# Placa_FdC_v2.net
KiCad netlist of a schematic drawn in Altium Designer
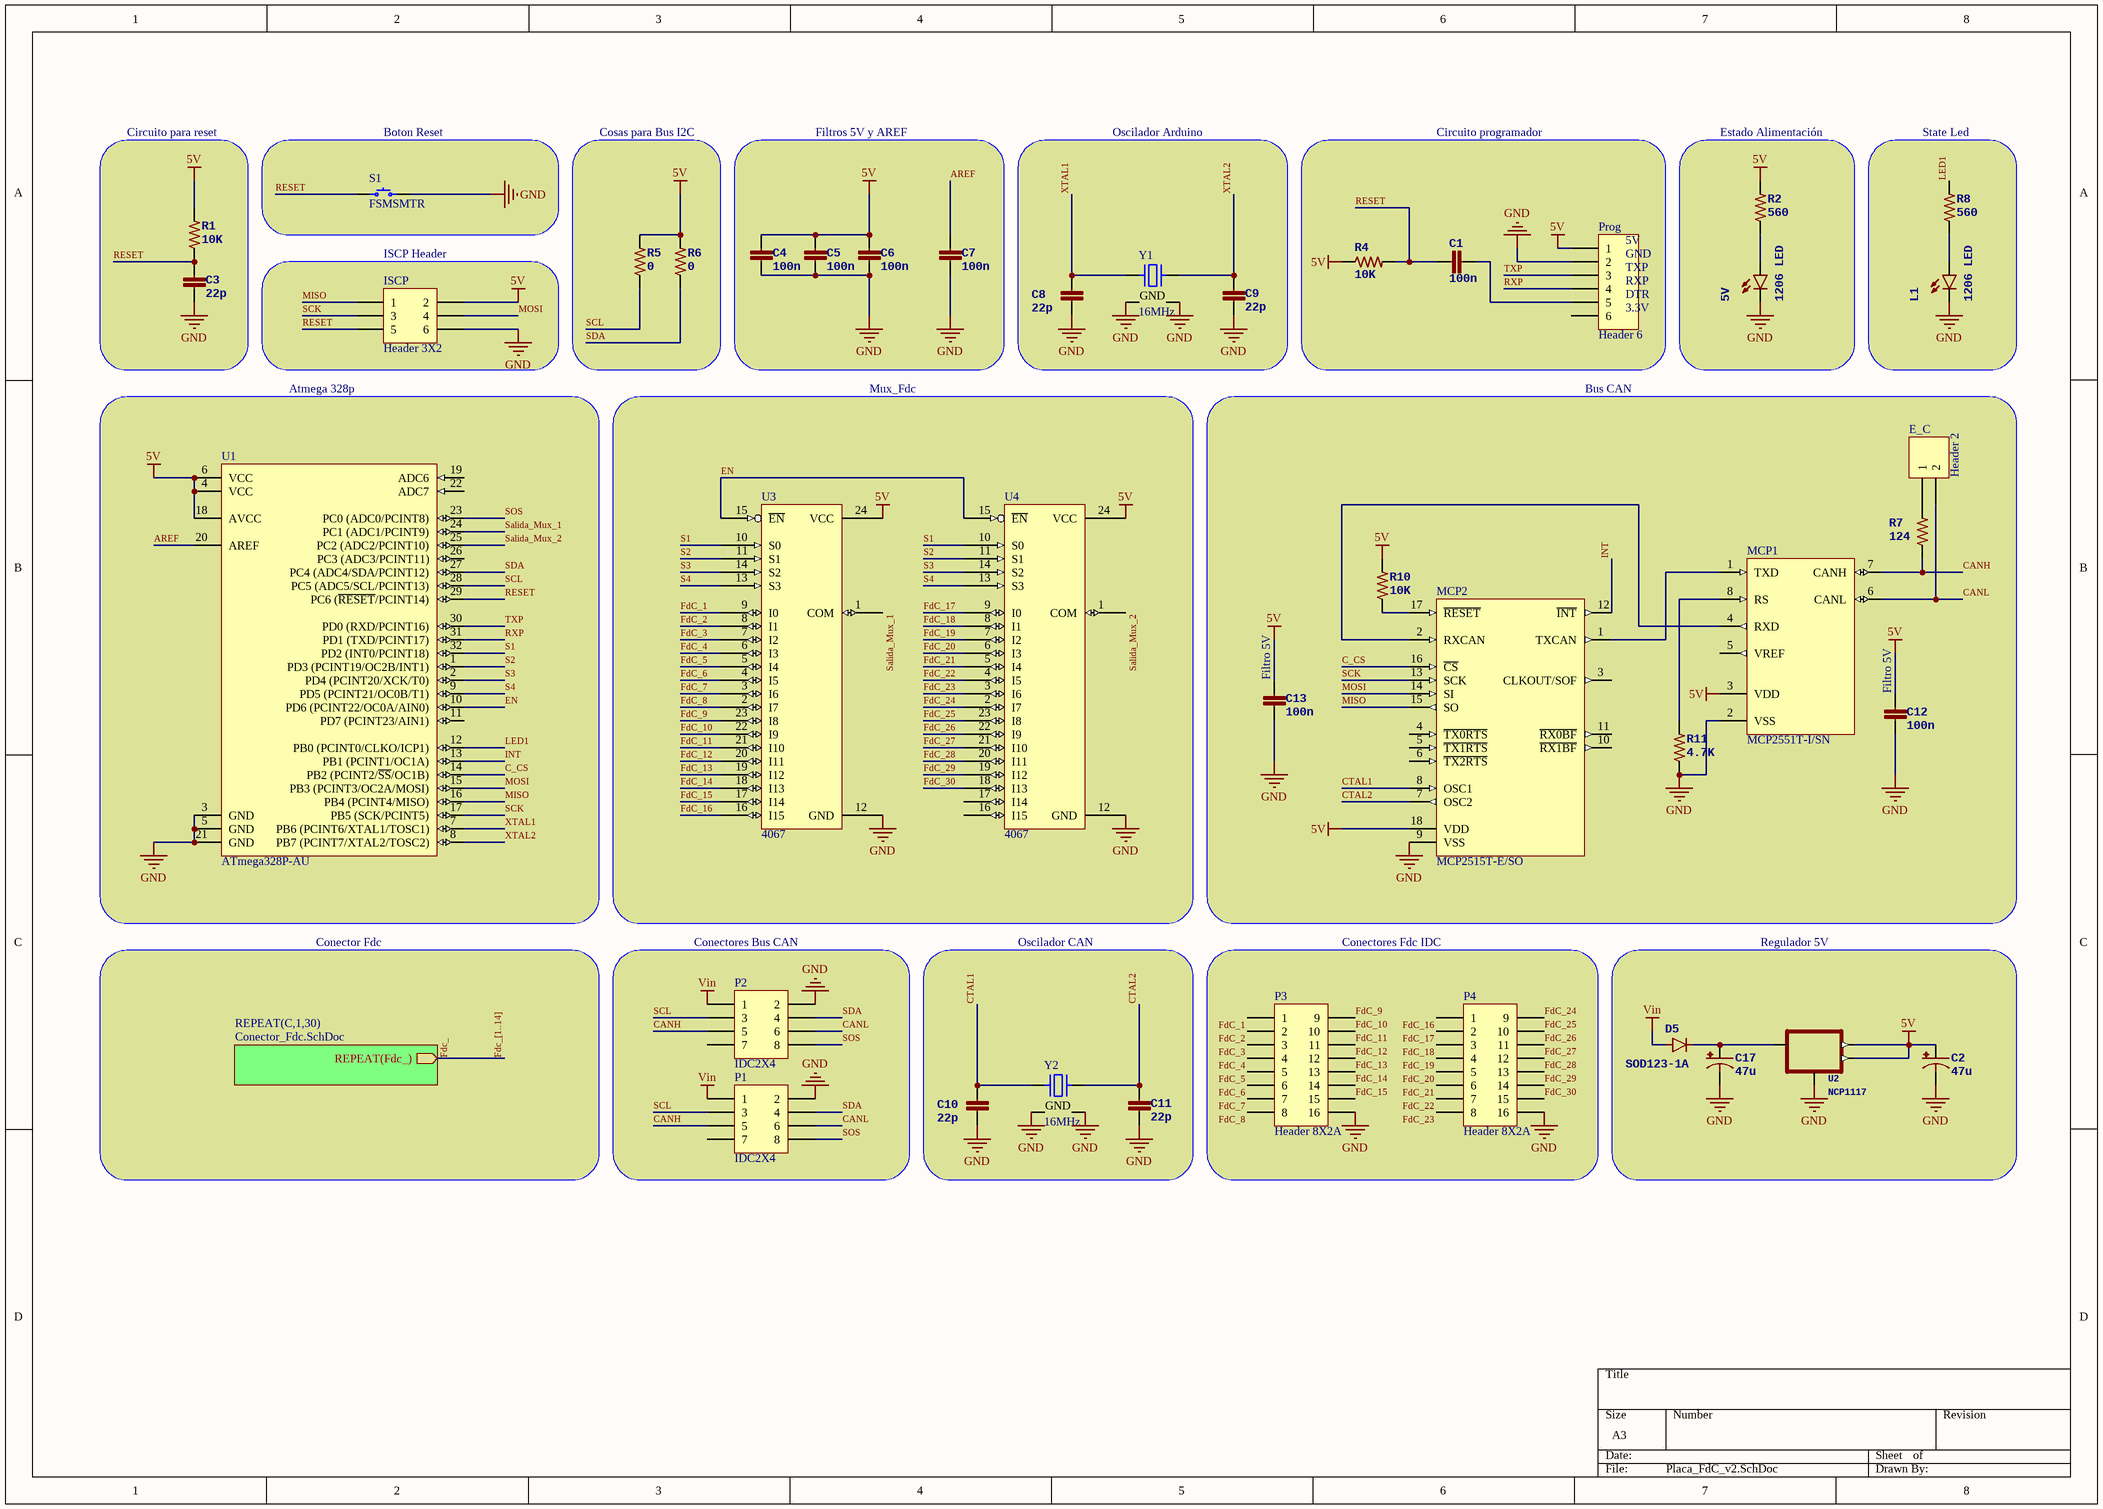
[diagram p0: Placa_FdC_v2.SchDoc]

(export (version "E")
  (design (tool "Eeschema 10.0.6"))
  (components
    (comp (ref "5V")
      (value "1206 LED")
      (footprint "SparkFun-LED:LED-1206")
      (libsource (lib "SparkFun-LED") (part "LED1206"))
    )
    (comp (ref "C1")
      (value "100n")
      (footprint "SparkFun-Passives:0805")
      (libsource (lib "") (part "CAP0805_1"))
    )
    (comp (ref "C2")
      (value "47u")
      (footprint "PANASONIC_D")
      (libsource (lib "SparkFun-Capacitors") (part "47UF-50V-20%(ELECT)"))
    )
    (comp (ref "C3")
      (value "22p")
      (footprint "SparkFun-Passives:0805")
      (libsource (lib "SparkFun-Passives") (part "CAP0805"))
    )
    (comp (ref "C4")
      (value "100n")
      (footprint "SparkFun-Passives:0805")
      (libsource (lib "SparkFun-Passives") (part "CAP0805"))
    )
    (comp (ref "C5")
      (value "100n")
      (footprint "SparkFun-Passives:0805")
      (libsource (lib "SparkFun-Passives") (part "CAP0805"))
    )
    (comp (ref "C6")
      (value "100n")
      (footprint "SparkFun-Passives:0805")
      (libsource (lib "SparkFun-Passives") (part "CAP0805"))
    )
    (comp (ref "C7")
      (value "100n")
      (footprint "SparkFun-Passives:0805")
      (libsource (lib "SparkFun-Passives") (part "CAP0805"))
    )
    (comp (ref "C8")
      (value "22p")
      (footprint "SparkFun-Passives:0805")
      (libsource (lib "SparkFun-Passives") (part "CAP0805"))
    )
    (comp (ref "C9")
      (value "22p")
      (footprint "SparkFun-Passives:0805")
      (libsource (lib "SparkFun-Passives") (part "CAP0805"))
    )
    (comp (ref "C10")
      (value "22p")
      (footprint "SparkFun-Passives:0805")
      (libsource (lib "SparkFun-Passives") (part "CAP0805"))
    )
    (comp (ref "C11")
      (value "22p")
      (footprint "SparkFun-Passives:0805")
      (libsource (lib "SparkFun-Passives") (part "CAP0805"))
    )
    (comp (ref "C12")
      (value "100n")
      (footprint "SparkFun-Passives:0805")
      (libsource (lib "SparkFun-Passives") (part "CAP0805"))
    )
    (comp (ref "C13")
      (value "100n")
      (footprint "SparkFun-Passives:0805")
      (libsource (lib "SparkFun-Passives") (part "CAP0805"))
    )
    (comp (ref "C17")
      (value "47u")
      (footprint "PANASONIC_D")
      (libsource (lib "SparkFun-Capacitors") (part "47UF-50V-20%(ELECT)"))
    )
    (comp (ref "D5")
      (value "SOD123-1A")
      (footprint "SOD-123")
      (libsource (lib "SparkFun-DiscreteSemi") (part "DIODESOD123"))
    )
    (comp (ref "E_C")
      (value "Header 2")
      (footprint "HDR1X2")
      (description "Header, 2-Pin")
      (fields (field (name "PUBLISHER") "Altium Limited"))
      (libsource (lib "Miscellaneous Connectors") (part "Header 2"))
    )
    (comp (ref "ISCP")
      (value "Header 3X2")
      (footprint "HDR2X3")
      (description "Header, 3-Pin, Dual row")
      (fields (field (name "PUBLISHER") "Altium Limited"))
      (libsource (lib "Miscellaneous Connectors") (part "Header 3X2"))
    )
    (comp (ref "L1")
      (value "1206 LED")
      (footprint "SparkFun-LED:LED-1206")
      (libsource (lib "SparkFun-LED") (part "LED1206"))
    )
    (comp (ref "MCP1")
      (value "MCP2551T-I/SN")
      (footprint "SOIC-SN8_N")
      (description "High-Speed CAN Transceiver, 8-Pin SOIC, Industrial Temperature, Tape and Reel")
      (fields (field (name "PUBLISHER") "Altium Limited"))
      (libsource (lib "Microchip Interface") (part "MCP2551T-I/SN"))
    )
    (comp (ref "MCP2")
      (value "MCP2515T-E/SO")
      (footprint "SOIC-SO18_N")
      (description "Stand-Alone CAN Controller With SPI Interface, 18-Pin SOIC, Extended Temperature, Tape and Reel")
      (fields (field (name "PUBLISHER") "Altium Limited"))
      (libsource (lib "Microchip Interface") (part "MCP2515T-E/SO"))
    )
    (comp (ref "P1")
      (value "IDC2X4")
      (footprint "IDC:IDC2X4")
      (description "Header, 4-Pin, Dual row")
      (fields (field (name "PUBLISHER") "Altium Limited"))
      (libsource (lib "IDC") (part "IDC2X4"))
    )
    (comp (ref "P2")
      (value "IDC2X4")
      (footprint "IDC:IDC2X4")
      (description "Header, 4-Pin, Dual row")
      (fields (field (name "PUBLISHER") "Altium Limited"))
      (libsource (lib "IDC") (part "IDC2X4"))
    )
    (comp (ref "P3")
      (value "Header 8X2A")
      (footprint "HDR2X8_CEN")
      (description "Header, 8-Pin, Dual row")
      (fields (field (name "PUBLISHER") "Altium Limited"))
      (libsource (lib "Miscellaneous Connectors") (part "Header 8X2A"))
    )
    (comp (ref "P4")
      (value "Header 8X2A")
      (footprint "HDR2X8_CEN")
      (description "Header, 8-Pin, Dual row")
      (fields (field (name "PUBLISHER") "Altium Limited"))
      (libsource (lib "Miscellaneous Connectors") (part "Header 8X2A"))
    )
    (comp (ref "Prog")
      (value "Header 6")
      (footprint "HDR1X6")
      (description "Header, 6-Pin")
      (fields (field (name "PUBLISHER") "Altium Limited"))
      (libsource (lib "Miscellaneous Connectors") (part "Header 6"))
    )
    (comp (ref "R1")
      (value "10K")
      (footprint "SparkFun-Passives:0805")
      (libsource (lib "SparkFun-Passives") (part "RESISTOR0805-RES"))
    )
    (comp (ref "R2")
      (value "560")
      (footprint "SparkFun-Passives:0805")
      (libsource (lib "SparkFun-Passives") (part "RESISTOR0805-RES"))
    )
    (comp (ref "R4")
      (value "10K")
      (footprint "SparkFun-Passives:0805")
      (libsource (lib "SparkFun-Passives") (part "RESISTOR0805-RES"))
    )
    (comp (ref "R5")
      (value "0")
      (footprint "SparkFun-Passives:0805")
      (libsource (lib "SparkFun-Passives") (part "RESISTOR0805-RES"))
    )
    (comp (ref "R6")
      (value "0")
      (footprint "SparkFun-Passives:0805")
      (libsource (lib "SparkFun-Passives") (part "RESISTOR0805-RES"))
    )
    (comp (ref "R7")
      (value "124")
      (footprint "SparkFun-Passives:0805")
      (libsource (lib "SparkFun-Passives") (part "RESISTOR0805-RES"))
    )
    (comp (ref "R8")
      (value "560")
      (footprint "SparkFun-Passives:0805")
      (libsource (lib "SparkFun-Passives") (part "RESISTOR0805-RES"))
    )
    (comp (ref "R10")
      (value "10K")
      (footprint "SparkFun-Passives:0805")
      (libsource (lib "SparkFun-Passives") (part "RESISTOR0805-RES"))
    )
    (comp (ref "R11")
      (value "4.7K")
      (footprint "SparkFun-Passives:0805")
      (libsource (lib "SparkFun-Passives") (part "RESISTOR0805-RES"))
    )
    (comp (ref "S1")
      (value "FSMSMTR")
      (footprint "TE FSMSMTR")
      (description "SWITCH TACTILE SPST-NO 0.05A 24V")
      (fields (field (name "MANUFACTURER") "TE Connectivity Alcoswitch Switches"))
      (libsource (lib "Button - Tactile") (part "SPST-NO 2 PIN"))
    )
    (comp (ref "U1")
      (value "ATmega328P-AU")
      (footprint "32A_N")
      (fields (field (name "PUBLISHER") "Altium Limited"))
      (libsource (lib "Atmel Microcontroller 8-Bit megaAVR") (part "ATmega328P-AU"))
    )
    (comp (ref "U2")
      (value "NCP1117")
      (footprint "SparkFun-IC-Power:SOT223")
      (libsource (lib "SparkFun-IC-Power") (part "V_REG_LM1117SOT223"))
    )
    (comp (ref "U3")
      (value "4067")
      (footprint "SSOP-24")
      (description "MUX-74HC4067")
      (libsource (lib "Mux") (part "MUX-74HC4067"))
    )
    (comp (ref "U4")
      (value "4067")
      (footprint "SSOP-24")
      (description "MUX-74HC4067")
      (libsource (lib "Mux") (part "MUX-74HC4067"))
    )
    (comp (ref "Y1")
      (value "16MHz")
      (footprint "NDK NX3225SA")
      (description "CRYSTAL 16.0000MHZ 8PF SMD")
      (fields (field (name "PART NUMBER") "NX3225SA-16.000MHZ-STD-CSR-1") (field (name "MANUFACTURER") "NDK"))
      (libsource (lib "Oscillator - Crystal") (part "NDK Crystal NX3225SA"))
    )
    (comp (ref "Y2")
      (value "16MHz")
      (footprint "NDK NX3225SA")
      (description "CRYSTAL 16.0000MHZ 8PF SMD")
      (fields (field (name "PART NUMBER") "NX3225SA-16.000MHZ-STD-CSR-1") (field (name "MANUFACTURER") "NDK"))
      (libsource (lib "Oscillator - Crystal") (part "NDK Crystal NX3225SA"))
    )
  )
  (nets
    (net (code "15") (name "/AREF") (class "Default")
      (node (ref "C7") (pin "1") (pinfunction "1_1") (pintype "passive"))
      (node (ref "U1") (pin "20") (pinfunction "AREF_20") (pintype "passive"))
    )
    (net (code "16") (name "/CANH") (class "Default")
      (node (ref "MCP1") (pin "7") (pinfunction "CANH_7") (pintype "bidirectional"))
      (node (ref "P1") (pin "5") (pinfunction "5_5") (pintype "passive"))
      (node (ref "P2") (pin "5") (pinfunction "5_5") (pintype "passive"))
      (node (ref "R7") (pin "1") (pinfunction "1_1") (pintype "passive"))
    )
    (net (code "17") (name "/CANL") (class "Default")
      (node (ref "E_C") (pin "2") (pinfunction "2_2") (pintype "passive"))
      (node (ref "MCP1") (pin "6") (pinfunction "CANL_6") (pintype "bidirectional"))
      (node (ref "P1") (pin "6") (pinfunction "6_6") (pintype "passive"))
      (node (ref "P2") (pin "6") (pinfunction "6_6") (pintype "passive"))
    )
    (net (code "18") (name "/CTAL1") (class "Default")
      (node (ref "C10") (pin "1") (pinfunction "1_1") (pintype "passive"))
      (node (ref "MCP2") (pin "8") (pinfunction "OSC1_8") (pintype "input"))
      (node (ref "Y2") (pin "1") (pinfunction "1_1") (pintype "passive"))
    )
    (net (code "19") (name "/CTAL2") (class "Default")
      (node (ref "C11") (pin "1") (pinfunction "1_1") (pintype "passive"))
      (node (ref "MCP2") (pin "7") (pinfunction "OSC2_7") (pintype "output"))
      (node (ref "Y2") (pin "3") (pinfunction "3_3") (pintype "passive"))
    )
    (net (code "20") (name "/C_CS") (class "Default")
      (node (ref "MCP2") (pin "16") (pinfunction "~{CS}_16") (pintype "input"))
      (node (ref "U1") (pin "14") (pinfunction "PB2_(PCINT2/~{SS}/OC1B)_14") (pintype "bidirectional"))
    )
    (net (code "21") (name "/EN") (class "Default")
      (node (ref "U1") (pin "10") (pinfunction "PD6_(PCINT22/OC0A/AIN0)_10") (pintype "bidirectional"))
      (node (ref "U3") (pin "15") (pinfunction "~{EN}_15") (pintype "input"))
      (node (ref "U4") (pin "15") (pinfunction "~{EN}_15") (pintype "input"))
    )
    (net (code "22") (name "/FdC_1") (class "Default")
      (node (ref "P3") (pin "1") (pinfunction "1_1") (pintype "passive"))
      (node (ref "U3") (pin "9") (pinfunction "I0_9") (pintype "bidirectional"))
    )
    (net (code "23") (name "/FdC_2") (class "Default")
      (node (ref "P3") (pin "2") (pinfunction "2_2") (pintype "passive"))
      (node (ref "U3") (pin "8") (pinfunction "I1_8") (pintype "bidirectional"))
    )
    (net (code "24") (name "/FdC_3") (class "Default")
      (node (ref "P3") (pin "3") (pinfunction "3_3") (pintype "passive"))
      (node (ref "U3") (pin "7") (pinfunction "I2_7") (pintype "bidirectional"))
    )
    (net (code "25") (name "/FdC_4") (class "Default")
      (node (ref "P3") (pin "4") (pinfunction "4_4") (pintype "passive"))
      (node (ref "U3") (pin "6") (pinfunction "I3_6") (pintype "bidirectional"))
    )
    (net (code "26") (name "/FdC_5") (class "Default")
      (node (ref "P3") (pin "5") (pinfunction "5_5") (pintype "passive"))
      (node (ref "U3") (pin "5") (pinfunction "I4_5") (pintype "bidirectional"))
    )
    (net (code "27") (name "/FdC_6") (class "Default")
      (node (ref "P3") (pin "6") (pinfunction "6_6") (pintype "passive"))
      (node (ref "U3") (pin "4") (pinfunction "I5_4") (pintype "bidirectional"))
    )
    (net (code "28") (name "/FdC_7") (class "Default")
      (node (ref "P3") (pin "7") (pinfunction "7_7") (pintype "passive"))
      (node (ref "U3") (pin "3") (pinfunction "I6_3") (pintype "bidirectional"))
    )
    (net (code "29") (name "/FdC_8") (class "Default")
      (node (ref "P3") (pin "8") (pinfunction "8_8") (pintype "passive"))
      (node (ref "U3") (pin "2") (pinfunction "I7_2") (pintype "bidirectional"))
    )
    (net (code "30") (name "/FdC_9") (class "Default")
      (node (ref "P3") (pin "9") (pinfunction "9_9") (pintype "passive"))
      (node (ref "U3") (pin "23") (pinfunction "I8_23") (pintype "bidirectional"))
    )
    (net (code "31") (name "/FdC_10") (class "Default")
      (node (ref "P3") (pin "10") (pinfunction "10_10") (pintype "passive"))
      (node (ref "U3") (pin "22") (pinfunction "I9_22") (pintype "bidirectional"))
    )
    (net (code "32") (name "/FdC_11") (class "Default")
      (node (ref "P3") (pin "11") (pinfunction "11_11") (pintype "passive"))
      (node (ref "U3") (pin "21") (pinfunction "I10_21") (pintype "bidirectional"))
    )
    (net (code "33") (name "/FdC_12") (class "Default")
      (node (ref "P3") (pin "12") (pinfunction "12_12") (pintype "passive"))
      (node (ref "U3") (pin "20") (pinfunction "I11_20") (pintype "bidirectional"))
    )
    (net (code "34") (name "/FdC_13") (class "Default")
      (node (ref "P3") (pin "13") (pinfunction "13_13") (pintype "passive"))
      (node (ref "U3") (pin "19") (pinfunction "I12_19") (pintype "bidirectional"))
    )
    (net (code "35") (name "/FdC_14") (class "Default")
      (node (ref "P3") (pin "14") (pinfunction "14_14") (pintype "passive"))
      (node (ref "U3") (pin "18") (pinfunction "I13_18") (pintype "bidirectional"))
    )
    (net (code "36") (name "/FdC_15") (class "Default")
      (node (ref "P3") (pin "15") (pinfunction "15_15") (pintype "passive"))
      (node (ref "U3") (pin "17") (pinfunction "I14_17") (pintype "bidirectional"))
    )
    (net (code "37") (name "/FdC_16") (class "Default")
      (node (ref "P4") (pin "1") (pinfunction "1_1") (pintype "passive"))
      (node (ref "U3") (pin "16") (pinfunction "I15_16") (pintype "bidirectional"))
    )
    (net (code "38") (name "/FdC_17") (class "Default")
      (node (ref "P4") (pin "2") (pinfunction "2_2") (pintype "passive"))
      (node (ref "U4") (pin "9") (pinfunction "I0_9") (pintype "bidirectional"))
    )
    (net (code "39") (name "/FdC_18") (class "Default")
      (node (ref "P4") (pin "3") (pinfunction "3_3") (pintype "passive"))
      (node (ref "U4") (pin "8") (pinfunction "I1_8") (pintype "bidirectional"))
    )
    (net (code "40") (name "/FdC_19") (class "Default")
      (node (ref "P4") (pin "4") (pinfunction "4_4") (pintype "passive"))
      (node (ref "U4") (pin "7") (pinfunction "I2_7") (pintype "bidirectional"))
    )
    (net (code "41") (name "/FdC_20") (class "Default")
      (node (ref "P4") (pin "5") (pinfunction "5_5") (pintype "passive"))
      (node (ref "U4") (pin "6") (pinfunction "I3_6") (pintype "bidirectional"))
    )
    (net (code "42") (name "/FdC_21") (class "Default")
      (node (ref "P4") (pin "6") (pinfunction "6_6") (pintype "passive"))
      (node (ref "U4") (pin "5") (pinfunction "I4_5") (pintype "bidirectional"))
    )
    (net (code "43") (name "/FdC_22") (class "Default")
      (node (ref "P4") (pin "7") (pinfunction "7_7") (pintype "passive"))
      (node (ref "U4") (pin "4") (pinfunction "I5_4") (pintype "bidirectional"))
    )
    (net (code "44") (name "/FdC_23") (class "Default")
      (node (ref "P4") (pin "8") (pinfunction "8_8") (pintype "passive"))
      (node (ref "U4") (pin "3") (pinfunction "I6_3") (pintype "bidirectional"))
    )
    (net (code "45") (name "/FdC_24") (class "Default")
      (node (ref "P4") (pin "9") (pinfunction "9_9") (pintype "passive"))
      (node (ref "U4") (pin "2") (pinfunction "I7_2") (pintype "bidirectional"))
    )
    (net (code "46") (name "/FdC_25") (class "Default")
      (node (ref "P4") (pin "10") (pinfunction "10_10") (pintype "passive"))
      (node (ref "U4") (pin "23") (pinfunction "I8_23") (pintype "bidirectional"))
    )
    (net (code "47") (name "/FdC_26") (class "Default")
      (node (ref "P4") (pin "11") (pinfunction "11_11") (pintype "passive"))
      (node (ref "U4") (pin "22") (pinfunction "I9_22") (pintype "bidirectional"))
    )
    (net (code "48") (name "/FdC_27") (class "Default")
      (node (ref "P4") (pin "12") (pinfunction "12_12") (pintype "passive"))
      (node (ref "U4") (pin "21") (pinfunction "I10_21") (pintype "bidirectional"))
    )
    (net (code "49") (name "/FdC_28") (class "Default")
      (node (ref "P4") (pin "13") (pinfunction "13_13") (pintype "passive"))
      (node (ref "U4") (pin "20") (pinfunction "I11_20") (pintype "bidirectional"))
    )
    (net (code "50") (name "/FdC_29") (class "Default")
      (node (ref "P4") (pin "14") (pinfunction "14_14") (pintype "passive"))
      (node (ref "U4") (pin "19") (pinfunction "I12_19") (pintype "bidirectional"))
    )
    (net (code "51") (name "/FdC_30") (class "Default")
      (node (ref "P4") (pin "15") (pinfunction "15_15") (pintype "passive"))
      (node (ref "U4") (pin "18") (pinfunction "I13_18") (pintype "bidirectional"))
    )
    (net (code "54") (name "/INT") (class "Default")
      (node (ref "MCP2") (pin "12") (pinfunction "~{INT}_12") (pintype "output"))
      (node (ref "U1") (pin "13") (pinfunction "PB1_(PCINT1/OC1A)_13") (pintype "bidirectional"))
    )
    (net (code "55") (name "/LED1") (class "Default")
      (node (ref "R8") (pin "2") (pinfunction "2_2") (pintype "passive"))
      (node (ref "U1") (pin "12") (pinfunction "PB0_(PCINT0/CLKO/ICP1)_12") (pintype "bidirectional"))
    )
    (net (code "56") (name "/MISO") (class "Default")
      (node (ref "ISCP") (pin "1") (pinfunction "1_1") (pintype "passive"))
      (node (ref "MCP2") (pin "15") (pinfunction "SO_15") (pintype "output"))
      (node (ref "U1") (pin "16") (pinfunction "PB4_(PCINT4/MISO)_16") (pintype "bidirectional"))
    )
    (net (code "57") (name "/MOSI") (class "Default")
      (node (ref "ISCP") (pin "4") (pinfunction "4_4") (pintype "passive"))
      (node (ref "MCP2") (pin "14") (pinfunction "SI_14") (pintype "input"))
      (node (ref "U1") (pin "15") (pinfunction "PB3_(PCINT3/OC2A/MOSI)_15") (pintype "bidirectional"))
    )
    (net (code "58") (name "/RESET") (class "Default")
      (node (ref "C1") (pin "1") (pinfunction "1_1") (pintype "passive"))
      (node (ref "C3") (pin "1") (pinfunction "1_1") (pintype "passive"))
      (node (ref "ISCP") (pin "5") (pinfunction "5_5") (pintype "passive"))
      (node (ref "R1") (pin "1") (pinfunction "1_1") (pintype "passive"))
      (node (ref "R4") (pin "2") (pinfunction "2_2") (pintype "passive"))
      (node (ref "S1") (pin "1") (pinfunction "1_1") (pintype "passive"))
      (node (ref "U1") (pin "29") (pinfunction "PC6_(~{RESET}/PCINT14)_29") (pintype "bidirectional"))
    )
    (net (code "59") (name "/RXP") (class "Default")
      (node (ref "Prog") (pin "4") (pinfunction "4_4") (pintype "passive"))
      (node (ref "U1") (pin "31") (pinfunction "PD1_(TXD/PCINT17)_31") (pintype "bidirectional"))
    )
    (net (code "60") (name "/S1") (class "Default")
      (node (ref "U1") (pin "32") (pinfunction "PD2_(INT0/PCINT18)_32") (pintype "bidirectional"))
      (node (ref "U3") (pin "10") (pinfunction "S0_10") (pintype "input"))
      (node (ref "U4") (pin "10") (pinfunction "S0_10") (pintype "input"))
    )
    (net (code "61") (name "/S2") (class "Default")
      (node (ref "U1") (pin "1") (pinfunction "PD3_(PCINT19/OC2B/INT1)_1") (pintype "bidirectional"))
      (node (ref "U3") (pin "11") (pinfunction "S1_11") (pintype "input"))
      (node (ref "U4") (pin "11") (pinfunction "S1_11") (pintype "input"))
    )
    (net (code "62") (name "/S3") (class "Default")
      (node (ref "U1") (pin "2") (pinfunction "PD4_(PCINT20/XCK/T0)_2") (pintype "bidirectional"))
      (node (ref "U3") (pin "14") (pinfunction "S2_14") (pintype "input"))
      (node (ref "U4") (pin "14") (pinfunction "S2_14") (pintype "input"))
    )
    (net (code "63") (name "/S4") (class "Default")
      (node (ref "U1") (pin "9") (pinfunction "PD5_(PCINT21/OC0B/T1)_9") (pintype "bidirectional"))
      (node (ref "U3") (pin "13") (pinfunction "S3_13") (pintype "input"))
      (node (ref "U4") (pin "13") (pinfunction "S3_13") (pintype "input"))
    )
    (net (code "64") (name "/SCK") (class "Default")
      (node (ref "ISCP") (pin "3") (pinfunction "3_3") (pintype "passive"))
      (node (ref "MCP2") (pin "13") (pinfunction "SCK_13") (pintype "input"))
      (node (ref "U1") (pin "17") (pinfunction "PB5_(SCK/PCINT5)_17") (pintype "bidirectional"))
    )
    (net (code "65") (name "/SCL") (class "Default")
      (node (ref "P1") (pin "3") (pinfunction "3_3") (pintype "passive"))
      (node (ref "P2") (pin "3") (pinfunction "3_3") (pintype "passive"))
      (node (ref "R5") (pin "1") (pinfunction "1_1") (pintype "passive"))
      (node (ref "U1") (pin "28") (pinfunction "PC5_(ADC5/SCL/PCINT13)_28") (pintype "bidirectional"))
    )
    (net (code "66") (name "/SDA") (class "Default")
      (node (ref "P1") (pin "4") (pinfunction "4_4") (pintype "passive"))
      (node (ref "P2") (pin "4") (pinfunction "4_4") (pintype "passive"))
      (node (ref "R6") (pin "1") (pinfunction "1_1") (pintype "passive"))
      (node (ref "U1") (pin "27") (pinfunction "PC4_(ADC4/SDA/PCINT12)_27") (pintype "bidirectional"))
    )
    (net (code "67") (name "/SOS") (class "Default")
      (node (ref "P1") (pin "8") (pinfunction "8_8") (pintype "passive"))
      (node (ref "P2") (pin "8") (pinfunction "8_8") (pintype "passive"))
      (node (ref "U1") (pin "23") (pinfunction "PC0_(ADC0/PCINT8)_23") (pintype "bidirectional"))
    )
    (net (code "68") (name "/Salida_Mux_1") (class "Default")
      (node (ref "U1") (pin "24") (pinfunction "PC1_(ADC1/PCINT9)_24") (pintype "bidirectional"))
      (node (ref "U3") (pin "1") (pinfunction "COM_1") (pintype "bidirectional"))
    )
    (net (code "69") (name "/Salida_Mux_2") (class "Default")
      (node (ref "U1") (pin "25") (pinfunction "PC2_(ADC2/PCINT10)_25") (pintype "bidirectional"))
      (node (ref "U4") (pin "1") (pinfunction "COM_1") (pintype "bidirectional"))
    )
    (net (code "70") (name "/TXP") (class "Default")
      (node (ref "Prog") (pin "3") (pinfunction "3_3") (pintype "passive"))
      (node (ref "U1") (pin "30") (pinfunction "PD0_(RXD/PCINT16)_30") (pintype "bidirectional"))
    )
    (net (code "71") (name "/XTAL1") (class "Default")
      (node (ref "C8") (pin "1") (pinfunction "1_1") (pintype "passive"))
      (node (ref "U1") (pin "7") (pinfunction "PB6_(PCINT6/XTAL1/TOSC1)_7") (pintype "bidirectional"))
      (node (ref "Y1") (pin "1") (pinfunction "1_1") (pintype "passive"))
    )
    (net (code "72") (name "/XTAL2") (class "Default")
      (node (ref "C9") (pin "1") (pinfunction "1_1") (pintype "passive"))
      (node (ref "U1") (pin "8") (pinfunction "PB7_(PCINT7/XTAL2/TOSC2)_8") (pintype "bidirectional"))
      (node (ref "Y1") (pin "3") (pinfunction "3_3") (pintype "passive"))
    )
    (net (code "73") (name "5V") (class "Default")
      (node (ref "C12") (pin "1") (pinfunction "1_1") (pintype "passive"))
      (node (ref "C13") (pin "1") (pinfunction "1_1") (pintype "passive"))
      (node (ref "C2") (pin "+") (pinfunction "+_+") (pintype "passive"))
      (node (ref "C4") (pin "1") (pinfunction "1_1") (pintype "passive"))
      (node (ref "C5") (pin "1") (pinfunction "1_1") (pintype "passive"))
      (node (ref "C6") (pin "1") (pinfunction "1_1") (pintype "passive"))
      (node (ref "ISCP") (pin "2") (pinfunction "2_2") (pintype "passive"))
      (node (ref "MCP1") (pin "3") (pinfunction "VDD_3") (pintype "power_in"))
      (node (ref "MCP2") (pin "18") (pinfunction "VDD_18") (pintype "power_in"))
      (node (ref "Prog") (pin "1") (pinfunction "1_1") (pintype "passive"))
      (node (ref "R1") (pin "2") (pinfunction "2_2") (pintype "passive"))
      (node (ref "R10") (pin "2") (pinfunction "2_2") (pintype "passive"))
      (node (ref "R2") (pin "2") (pinfunction "2_2") (pintype "passive"))
      (node (ref "R4") (pin "1") (pinfunction "1_1") (pintype "passive"))
      (node (ref "R5") (pin "2") (pinfunction "2_2") (pintype "passive"))
      (node (ref "R6") (pin "2") (pinfunction "2_2") (pintype "passive"))
      (node (ref "U1") (pin "18") (pinfunction "AVCC_18") (pintype "power_in"))
      (node (ref "U1") (pin "4") (pinfunction "VCC_4") (pintype "power_in"))
      (node (ref "U1") (pin "6") (pinfunction "VCC_6") (pintype "power_in"))
      (node (ref "U2") (pin "2") (pinfunction "OUT_2") (pintype "output"))
      (node (ref "U2") (pin "4") (pinfunction "OUT@1_4") (pintype "output"))
      (node (ref "U3") (pin "24") (pinfunction "VCC_24") (pintype "power_in"))
      (node (ref "U4") (pin "24") (pinfunction "VCC_24") (pintype "power_in"))
    )
    (net (code "74") (name "GND") (class "Default")
      (node (ref "5V") (pin "C") (pinfunction "C_C") (pintype "passive"))
      (node (ref "C10") (pin "2") (pinfunction "2_2") (pintype "passive"))
      (node (ref "C11") (pin "2") (pinfunction "2_2") (pintype "passive"))
      (node (ref "C12") (pin "2") (pinfunction "2_2") (pintype "passive"))
      (node (ref "C13") (pin "2") (pinfunction "2_2") (pintype "passive"))
      (node (ref "C17") (pin "-") (pinfunction "-_-") (pintype "passive"))
      (node (ref "C2") (pin "-") (pinfunction "-_-") (pintype "passive"))
      (node (ref "C3") (pin "2") (pinfunction "2_2") (pintype "passive"))
      (node (ref "C4") (pin "2") (pinfunction "2_2") (pintype "passive"))
      (node (ref "C5") (pin "2") (pinfunction "2_2") (pintype "passive"))
      (node (ref "C6") (pin "2") (pinfunction "2_2") (pintype "passive"))
      (node (ref "C7") (pin "2") (pinfunction "2_2") (pintype "passive"))
      (node (ref "C8") (pin "2") (pinfunction "2_2") (pintype "passive"))
      (node (ref "C9") (pin "2") (pinfunction "2_2") (pintype "passive"))
      (node (ref "ISCP") (pin "6") (pinfunction "6_6") (pintype "passive"))
      (node (ref "L1") (pin "C") (pinfunction "C_C") (pintype "passive"))
      (node (ref "MCP1") (pin "2") (pinfunction "VSS_2") (pintype "power_in"))
      (node (ref "MCP2") (pin "9") (pinfunction "VSS_9") (pintype "power_in"))
      (node (ref "P1") (pin "2") (pinfunction "2_2") (pintype "passive"))
      (node (ref "P2") (pin "2") (pinfunction "2_2") (pintype "passive"))
      (node (ref "P3") (pin "16") (pinfunction "16_16") (pintype "passive"))
      (node (ref "P4") (pin "16") (pinfunction "16_16") (pintype "passive"))
      (node (ref "Prog") (pin "2") (pinfunction "2_2") (pintype "passive"))
      (node (ref "R11") (pin "1") (pinfunction "1_1") (pintype "passive"))
      (node (ref "S1") (pin "2") (pinfunction "2_2") (pintype "passive"))
      (node (ref "U1") (pin "21") (pinfunction "GND_21") (pintype "power_in"))
      (node (ref "U1") (pin "3") (pinfunction "GND_3") (pintype "power_in"))
      (node (ref "U1") (pin "5") (pinfunction "GND_5") (pintype "power_in"))
      (node (ref "U2") (pin "1") (pinfunction "ADJ_1") (pintype "passive"))
      (node (ref "U3") (pin "12") (pinfunction "GND_12") (pintype "power_in"))
      (node (ref "U4") (pin "12") (pinfunction "GND_12") (pintype "power_in"))
      (node (ref "Y1") (pin "2") (pinfunction "GND_2") (pintype "passive"))
      (node (ref "Y1") (pin "4") (pinfunction "GND_4") (pintype "passive"))
      (node (ref "Y2") (pin "2") (pinfunction "GND_2") (pintype "passive"))
      (node (ref "Y2") (pin "4") (pinfunction "GND_4") (pintype "passive"))
    )
    (net (code "75") (name "Net-(5V-PadA)") (class "Default")
      (node (ref "5V") (pin "A") (pinfunction "A_A") (pintype "passive"))
      (node (ref "R2") (pin "1") (pinfunction "1_1") (pintype "passive"))
    )
    (net (code "76") (name "Net-(C1-Pad2)") (class "Default")
      (node (ref "C1") (pin "2") (pinfunction "2_2") (pintype "passive"))
      (node (ref "Prog") (pin "5") (pinfunction "5_5") (pintype "passive"))
    )
    (net (code "77") (name "Net-(E_C-Pad1)") (class "Default")
      (node (ref "E_C") (pin "1") (pinfunction "1_1") (pintype "passive"))
      (node (ref "R7") (pin "2") (pinfunction "2_2") (pintype "passive"))
    )
    (net (code "78") (name "Net-(L1-PadA)") (class "Default")
      (node (ref "L1") (pin "A") (pinfunction "A_A") (pintype "passive"))
      (node (ref "R8") (pin "1") (pinfunction "1_1") (pintype "passive"))
    )
    (net (code "79") (name "Net-(MCP1-RS)") (class "Default")
      (node (ref "MCP1") (pin "8") (pinfunction "RS_8") (pintype "input"))
      (node (ref "R11") (pin "2") (pinfunction "2_2") (pintype "passive"))
    )
    (net (code "80") (name "Net-(MCP1-RXD)") (class "Default")
      (node (ref "MCP1") (pin "4") (pinfunction "RXD_4") (pintype "output"))
      (node (ref "MCP2") (pin "2") (pinfunction "RXCAN_2") (pintype "input"))
    )
    (net (code "81") (name "Net-(MCP1-TXD)") (class "Default")
      (node (ref "MCP1") (pin "1") (pinfunction "TXD_1") (pintype "input"))
      (node (ref "MCP2") (pin "1") (pinfunction "TXCAN_1") (pintype "output"))
    )
    (net (code "82") (name "Net-(MCP2-~{RESET})") (class "Default")
      (node (ref "MCP2") (pin "17") (pinfunction "~{RESET}_17") (pintype "input"))
      (node (ref "R10") (pin "1") (pinfunction "1_1") (pintype "passive"))
    )
    (net (code "83") (name "Net-(U2-IN)") (class "Default")
      (node (ref "C17") (pin "+") (pinfunction "+_+") (pintype "passive"))
      (node (ref "D5") (pin "C") (pinfunction "C_C") (pintype "passive"))
      (node (ref "U2") (pin "3") (pinfunction "IN_3") (pintype "passive"))
    )
    (net (code "84") (name "Vin") (class "Default")
      (node (ref "D5") (pin "A") (pinfunction "A_A") (pintype "passive"))
      (node (ref "P1") (pin "1") (pinfunction "1_1") (pintype "passive"))
      (node (ref "P2") (pin "1") (pinfunction "1_1") (pintype "passive"))
    )
    (net (code "85") (name "unconnected-(MCP1-VREF-Pad5)") (class "Default")
      (node (ref "MCP1") (pin "5") (pinfunction "VREF_5") (pintype "output"))
    )
    (net (code "86") (name "unconnected-(MCP2-CLKOUT{slash}SOF-Pad3)") (class "Default")
      (node (ref "MCP2") (pin "3") (pinfunction "CLKOUT/SOF_3") (pintype "output"))
    )
    (net (code "87") (name "unconnected-(MCP2-~{RX0BF}-Pad11)") (class "Default")
      (node (ref "MCP2") (pin "11") (pinfunction "~{RX0BF}_11") (pintype "output"))
    )
    (net (code "88") (name "unconnected-(MCP2-~{RX1BF}-Pad10)") (class "Default")
      (node (ref "MCP2") (pin "10") (pinfunction "~{RX1BF}_10") (pintype "output"))
    )
    (net (code "89") (name "unconnected-(MCP2-~{TX0RTS}-Pad4)") (class "Default")
      (node (ref "MCP2") (pin "4") (pinfunction "~{TX0RTS}_4") (pintype "input"))
    )
    (net (code "90") (name "unconnected-(MCP2-~{TX1RTS}-Pad5)") (class "Default")
      (node (ref "MCP2") (pin "5") (pinfunction "~{TX1RTS}_5") (pintype "input"))
    )
    (net (code "91") (name "unconnected-(MCP2-~{TX2RTS}-Pad6)") (class "Default")
      (node (ref "MCP2") (pin "6") (pinfunction "~{TX2RTS}_6") (pintype "input"))
    )
    (net (code "92") (name "unconnected-(P1-Pad7)") (class "Default")
      (node (ref "P1") (pin "7") (pinfunction "7_7") (pintype "passive"))
    )
    (net (code "93") (name "unconnected-(P2-Pad7)") (class "Default")
      (node (ref "P2") (pin "7") (pinfunction "7_7") (pintype "passive"))
    )
    (net (code "94") (name "unconnected-(Prog-Pad6)") (class "Default")
      (node (ref "Prog") (pin "6") (pinfunction "6_6") (pintype "passive"))
    )
    (net (code "95") (name "unconnected-(U1-ADC6-Pad19)") (class "Default")
      (node (ref "U1") (pin "19") (pinfunction "ADC6_19") (pintype "input"))
    )
    (net (code "96") (name "unconnected-(U1-ADC7-Pad22)") (class "Default")
      (node (ref "U1") (pin "22") (pinfunction "ADC7_22") (pintype "input"))
    )
    (net (code "97") (name "unconnected-(U1-PC3_(ADC3{slash}PCINT11)-Pad26)") (class "Default")
      (node (ref "U1") (pin "26") (pinfunction "PC3_(ADC3/PCINT11)_26") (pintype "bidirectional"))
    )
    (net (code "98") (name "unconnected-(U1-PD7_(PCINT23{slash}AIN1)-Pad11)") (class "Default")
      (node (ref "U1") (pin "11") (pinfunction "PD7_(PCINT23/AIN1)_11") (pintype "bidirectional"))
    )
    (net (code "99") (name "unconnected-(U4-I14-Pad17)") (class "Default")
      (node (ref "U4") (pin "17") (pinfunction "I14_17") (pintype "bidirectional"))
    )
    (net (code "100") (name "unconnected-(U4-I15-Pad16)") (class "Default")
      (node (ref "U4") (pin "16") (pinfunction "I15_16") (pintype "bidirectional"))
    )
  )
)
